# p0-001.net
KiCad netlist of a schematic drawn in EAGLE
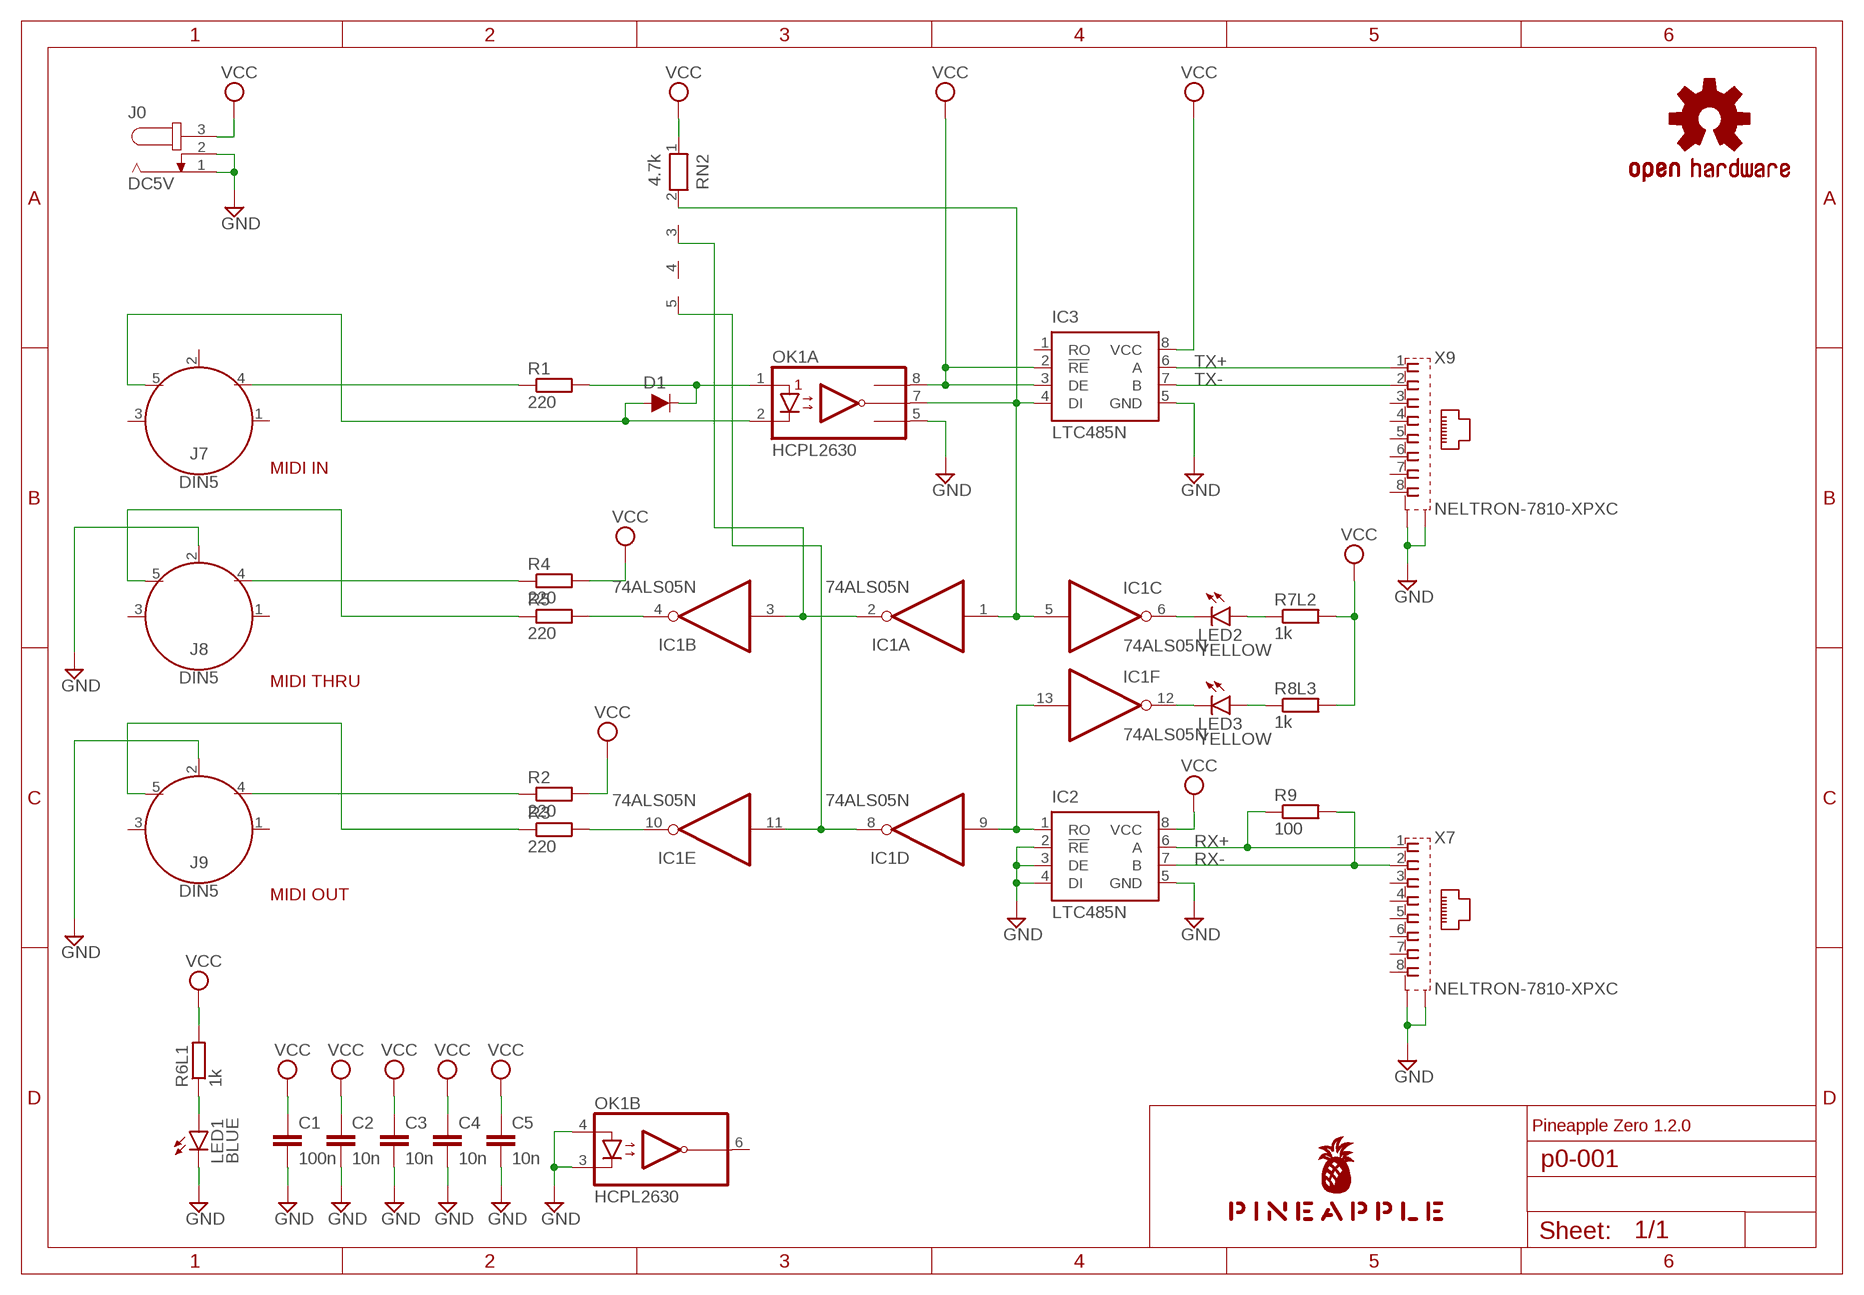
[diagram p0: schematic, sheet 1]

(export (version "E")
  (design (tool "Eeschema 10.0.6"))
  (components
    (comp (ref "C1")
      (value "100n")
      (footprint "eagle-import:C025-024X044")
      (libsource (lib "eagle-import") (part "C-EU025-024X044"))
    )
    (comp (ref "C2")
      (value "10n")
      (footprint "eagle-import:C025-024X044")
      (libsource (lib "eagle-import") (part "C-EU025-024X044"))
    )
    (comp (ref "C3")
      (value "10n")
      (footprint "eagle-import:C025-024X044")
      (libsource (lib "eagle-import") (part "C-EU025-024X044"))
    )
    (comp (ref "C4")
      (value "10n")
      (footprint "eagle-import:C025-024X044")
      (libsource (lib "eagle-import") (part "C-EU025-024X044"))
    )
    (comp (ref "C5")
      (value "10n")
      (footprint "eagle-import:C025-024X044")
      (libsource (lib "eagle-import") (part "C-EU025-024X044"))
    )
    (comp (ref "D1")
      (value "DIODE-1N4148")
      (footprint "eagle-import:DIODE-1N4148")
      (libsource (lib "eagle-import") (part "DIODE-1N4148"))
    )
    (comp (ref "IC1")
      (value "74ALS05N")
      (footprint "eagle-import:DIL14")
      (libsource (lib "eagle-import") (part "7405NALS"))
    )
    (comp (ref "IC2")
      (value "LTC485N")
      (footprint "eagle-import:DIL08")
      (libsource (lib "eagle-import") (part "LTC485N"))
    )
    (comp (ref "IC3")
      (value "LTC485N")
      (footprint "eagle-import:DIL08")
      (libsource (lib "eagle-import") (part "LTC485N"))
    )
    (comp (ref "J0")
      (value "DC5V")
      (footprint "eagle-import:SPC4077")
      (libsource (lib "eagle-import") (part "JACK-PLUG0"))
    )
    (comp (ref "J7")
      (value "DIN5")
      (footprint "eagle-import:DIN5-RA-PTH")
      (libsource (lib "eagle-import") (part "DIN5"))
    )
    (comp (ref "J8")
      (value "DIN5")
      (footprint "eagle-import:DIN5-RA-PTH")
      (libsource (lib "eagle-import") (part "DIN5"))
    )
    (comp (ref "J9")
      (value "DIN5")
      (footprint "eagle-import:DIN5-RA-PTH")
      (libsource (lib "eagle-import") (part "DIN5"))
    )
    (comp (ref "LED1")
      (value "BLUE")
      (footprint "eagle-import:LED3MM")
      (libsource (lib "eagle-import") (part "LED3MM"))
    )
    (comp (ref "LED2")
      (value "YELLOW")
      (footprint "eagle-import:LED3MM")
      (libsource (lib "eagle-import") (part "LED3MM"))
    )
    (comp (ref "LED3")
      (value "YELLOW")
      (footprint "eagle-import:LED3MM")
      (libsource (lib "eagle-import") (part "LED3MM"))
    )
    (comp (ref "LOGO1")
      (value "OSHW-LOGOS-COPPER")
      (footprint "eagle-import:OSHW-LOGO-S_COPPER")
      (libsource (lib "eagle-import") (part "OSHW-LOGOS-COPPER"))
    )
    (comp (ref "OK1")
      (value "HCPL2630")
      (footprint "eagle-import:DIL08")
      (fields (field (name "MF") "AGILENT TECHNOLOGIES") (field (name "MPN") "HCPL-2630-000E"))
      (libsource (lib "eagle-import") (part "HCPL2630"))
    )
    (comp (ref "R1")
      (value "220")
      (footprint "eagle-import:0204_5")
      (libsource (lib "eagle-import") (part "R-EU_0204/5"))
    )
    (comp (ref "R2")
      (value "220")
      (footprint "eagle-import:0204_5")
      (libsource (lib "eagle-import") (part "R-EU_0204/5"))
    )
    (comp (ref "R3")
      (value "220")
      (footprint "eagle-import:0204_5")
      (libsource (lib "eagle-import") (part "R-EU_0204/5"))
    )
    (comp (ref "R4")
      (value "220")
      (footprint "eagle-import:0204_5")
      (libsource (lib "eagle-import") (part "R-EU_0204/5"))
    )
    (comp (ref "R5")
      (value "220")
      (footprint "eagle-import:0204_5")
      (libsource (lib "eagle-import") (part "R-EU_0204/5"))
    )
    (comp (ref "R6L1")
      (value "1k")
      (footprint "eagle-import:0204_5")
      (libsource (lib "eagle-import") (part "R-EU_0204/5"))
    )
    (comp (ref "R7L2")
      (value "1k")
      (footprint "eagle-import:0204_5")
      (libsource (lib "eagle-import") (part "R-EU_0204/5"))
    )
    (comp (ref "R8L3")
      (value "1k")
      (footprint "eagle-import:0204_5")
      (libsource (lib "eagle-import") (part "R-EU_0204/5"))
    )
    (comp (ref "R9")
      (value "100")
      (footprint "eagle-import:0204_5")
      (libsource (lib "eagle-import") (part "R-EU_0204/5"))
    )
    (comp (ref "RN2")
      (value "4.7k")
      (footprint "eagle-import:RN-5")
      (libsource (lib "eagle-import") (part "RN04"))
    )
    (comp (ref "U$1")
      (value "PINEAPPLE450")
      (footprint "eagle-import:PINEAPPLE450")
      (libsource (lib "eagle-import") (part "PINEAPPLE450"))
    )
    (comp (ref "X7")
      (value "NELTRON-7810-XPXC")
      (footprint "eagle-import:NELTRON-7810-XPXC-FOOTPRINT")
      (libsource (lib "eagle-import") (part "NELTRON-7810-XPXC"))
    )
    (comp (ref "X9")
      (value "NELTRON-7810-XPXC")
      (footprint "eagle-import:NELTRON-7810-XPXC-FOOTPRINT")
      (libsource (lib "eagle-import") (part "NELTRON-7810-XPXC"))
    )
  )
  (nets
    (net (code "1") (name "/RX+") (class "Default")
      (node (ref "IC2") (pin "6") (pinfunction "A_6") (pintype "bidirectional"))
      (node (ref "R9") (pin "1") (pinfunction "1_1") (pintype "passive"))
      (node (ref "X7") (pin "1") (pinfunction "1_1") (pintype "passive"))
    )
    (net (code "2") (name "/RX-") (class "Default")
      (node (ref "IC2") (pin "7") (pinfunction "B_7") (pintype "bidirectional"))
      (node (ref "R9") (pin "2") (pinfunction "2_2") (pintype "passive"))
      (node (ref "X7") (pin "2") (pinfunction "2_2") (pintype "passive"))
    )
    (net (code "3") (name "/TX+") (class "Default")
      (node (ref "IC3") (pin "6") (pinfunction "A_6") (pintype "bidirectional"))
      (node (ref "X9") (pin "1") (pinfunction "1_1") (pintype "passive"))
    )
    (net (code "4") (name "/TX-") (class "Default")
      (node (ref "IC3") (pin "7") (pinfunction "B_7") (pintype "bidirectional"))
      (node (ref "X9") (pin "2") (pinfunction "2_2") (pintype "passive"))
    )
    (net (code "5") (name "GND") (class "Default")
      (node (ref "C1") (pin "2") (pinfunction "2_2") (pintype "passive"))
      (node (ref "C2") (pin "2") (pinfunction "2_2") (pintype "passive"))
      (node (ref "C3") (pin "2") (pinfunction "2_2") (pintype "passive"))
      (node (ref "C4") (pin "2") (pinfunction "2_2") (pintype "passive"))
      (node (ref "C5") (pin "2") (pinfunction "2_2") (pintype "passive"))
      (node (ref "IC2") (pin "2") (pinfunction "~{RE}_2") (pintype "input"))
      (node (ref "IC2") (pin "3") (pinfunction "DE_3") (pintype "input"))
      (node (ref "IC2") (pin "4") (pinfunction "DI_4") (pintype "input"))
      (node (ref "IC2") (pin "5") (pinfunction "GND_5") (pintype "input"))
      (node (ref "IC3") (pin "5") (pinfunction "GND_5") (pintype "input"))
      (node (ref "J0") (pin "1") (pinfunction "1_1") (pintype "passive"))
      (node (ref "J0") (pin "2") (pinfunction "2_2") (pintype "passive"))
      (node (ref "J8") (pin "2") (pinfunction "2_2") (pintype "bidirectional"))
      (node (ref "J9") (pin "2") (pinfunction "2_2") (pintype "bidirectional"))
      (node (ref "LED1") (pin "K") (pinfunction "C_K") (pintype "passive"))
      (node (ref "OK1") (pin "3") (pinfunction "C2_3") (pintype "passive"))
      (node (ref "OK1") (pin "4") (pinfunction "A2_4") (pintype "passive"))
      (node (ref "OK1") (pin "5") (pinfunction "GND_5") (pintype "passive"))
      (node (ref "X7") (pin "S1") (pinfunction "S1_S1") (pintype "passive"))
      (node (ref "X7") (pin "S2") (pinfunction "S2_S2") (pintype "passive"))
      (node (ref "X9") (pin "S1") (pinfunction "S1_S1") (pintype "passive"))
      (node (ref "X9") (pin "S2") (pinfunction "S2_S2") (pintype "passive"))
    )
    (net (code "6") (name "Net-(IC1A-I)") (class "Default")
      (node (ref "IC1") (pin "1") (pinfunction "I_1") (pintype "input"))
      (node (ref "IC1") (pin "5") (pinfunction "I_5") (pintype "input"))
      (node (ref "IC3") (pin "4") (pinfunction "DI_4") (pintype "input"))
      (node (ref "OK1") (pin "7") (pinfunction "VO1_7") (pintype "passive"))
      (node (ref "RN2") (pin "2") (pinfunction "2_2") (pintype "passive"))
    )
    (net (code "7") (name "Net-(IC1A-O)") (class "Default")
      (node (ref "IC1") (pin "2") (pinfunction "O_2") (pintype "open_collector"))
      (node (ref "IC1") (pin "3") (pinfunction "I_3") (pintype "input"))
      (node (ref "RN2") (pin "3") (pinfunction "3_3") (pintype "passive"))
    )
    (net (code "8") (name "Net-(IC1B-O)") (class "Default")
      (node (ref "IC1") (pin "4") (pinfunction "O_4") (pintype "open_collector"))
      (node (ref "R5") (pin "2") (pinfunction "2_2") (pintype "passive"))
    )
    (net (code "9") (name "Net-(IC1C-O)") (class "Default")
      (node (ref "IC1") (pin "6") (pinfunction "O_6") (pintype "open_collector"))
      (node (ref "LED2") (pin "K") (pinfunction "C_K") (pintype "passive"))
    )
    (net (code "10") (name "Net-(IC1D-I)") (class "Default")
      (node (ref "IC1") (pin "13") (pinfunction "I_13") (pintype "input"))
      (node (ref "IC1") (pin "9") (pinfunction "I_9") (pintype "input"))
      (node (ref "IC2") (pin "1") (pinfunction "RO_1") (pintype "output"))
    )
    (net (code "11") (name "Net-(IC1D-O)") (class "Default")
      (node (ref "IC1") (pin "11") (pinfunction "I_11") (pintype "input"))
      (node (ref "IC1") (pin "8") (pinfunction "O_8") (pintype "open_collector"))
      (node (ref "RN2") (pin "5") (pinfunction "5_5") (pintype "passive"))
    )
    (net (code "12") (name "Net-(IC1E-O)") (class "Default")
      (node (ref "IC1") (pin "10") (pinfunction "O_10") (pintype "open_collector"))
      (node (ref "R3") (pin "2") (pinfunction "2_2") (pintype "passive"))
    )
    (net (code "13") (name "Net-(IC1F-O)") (class "Default")
      (node (ref "IC1") (pin "12") (pinfunction "O_12") (pintype "open_collector"))
      (node (ref "LED3") (pin "K") (pinfunction "C_K") (pintype "passive"))
    )
    (net (code "14") (name "Net-(J7-Pad4)") (class "Default")
      (node (ref "J7") (pin "4") (pinfunction "4_4") (pintype "bidirectional"))
      (node (ref "R1") (pin "1") (pinfunction "1_1") (pintype "passive"))
    )
    (net (code "15") (name "Net-(J8-Pad4)") (class "Default")
      (node (ref "J8") (pin "4") (pinfunction "4_4") (pintype "bidirectional"))
      (node (ref "R4") (pin "1") (pinfunction "1_1") (pintype "passive"))
    )
    (net (code "16") (name "Net-(J8-Pad5)") (class "Default")
      (node (ref "J8") (pin "5") (pinfunction "5_5") (pintype "bidirectional"))
      (node (ref "R5") (pin "1") (pinfunction "1_1") (pintype "passive"))
    )
    (net (code "17") (name "Net-(J9-Pad4)") (class "Default")
      (node (ref "J9") (pin "4") (pinfunction "4_4") (pintype "bidirectional"))
      (node (ref "R2") (pin "1") (pinfunction "1_1") (pintype "passive"))
    )
    (net (code "18") (name "Net-(J9-Pad5)") (class "Default")
      (node (ref "J9") (pin "5") (pinfunction "5_5") (pintype "bidirectional"))
      (node (ref "R3") (pin "1") (pinfunction "1_1") (pintype "passive"))
    )
    (net (code "19") (name "Net-(LED1-PadA)") (class "Default")
      (node (ref "LED1") (pin "A") (pinfunction "A_A") (pintype "passive"))
      (node (ref "R6L1") (pin "1") (pinfunction "1_1") (pintype "passive"))
    )
    (net (code "20") (name "Net-(LED2-PadA)") (class "Default")
      (node (ref "LED2") (pin "A") (pinfunction "A_A") (pintype "passive"))
      (node (ref "R7L2") (pin "1") (pinfunction "1_1") (pintype "passive"))
    )
    (net (code "21") (name "Net-(LED3-PadA)") (class "Default")
      (node (ref "LED3") (pin "A") (pinfunction "A_A") (pintype "passive"))
      (node (ref "R8L3") (pin "1") (pinfunction "1_1") (pintype "passive"))
    )
    (net (code "22") (name "Net-(OK1A-A1)") (class "Default")
      (node (ref "D1") (pin "C") (pinfunction "C_C") (pintype "passive"))
      (node (ref "OK1") (pin "1") (pinfunction "A1_1") (pintype "passive"))
      (node (ref "R1") (pin "2") (pinfunction "2_2") (pintype "passive"))
    )
    (net (code "23") (name "Net-(OK1A-C1)") (class "Default")
      (node (ref "D1") (pin "A") (pinfunction "A_A") (pintype "passive"))
      (node (ref "J7") (pin "5") (pinfunction "5_5") (pintype "bidirectional"))
      (node (ref "OK1") (pin "2") (pinfunction "C1_2") (pintype "passive"))
    )
    (net (code "24") (name "VCC") (class "Default")
      (node (ref "C1") (pin "1") (pinfunction "1_1") (pintype "passive"))
      (node (ref "C2") (pin "1") (pinfunction "1_1") (pintype "passive"))
      (node (ref "C3") (pin "1") (pinfunction "1_1") (pintype "passive"))
      (node (ref "C4") (pin "1") (pinfunction "1_1") (pintype "passive"))
      (node (ref "C5") (pin "1") (pinfunction "1_1") (pintype "passive"))
      (node (ref "IC2") (pin "8") (pinfunction "VCC_8") (pintype "input"))
      (node (ref "IC3") (pin "2") (pinfunction "~{RE}_2") (pintype "input"))
      (node (ref "IC3") (pin "3") (pinfunction "DE_3") (pintype "input"))
      (node (ref "IC3") (pin "8") (pinfunction "VCC_8") (pintype "input"))
      (node (ref "J0") (pin "3") (pinfunction "3_3") (pintype "passive"))
      (node (ref "OK1") (pin "8") (pinfunction "VCC_8") (pintype "passive"))
      (node (ref "R2") (pin "2") (pinfunction "2_2") (pintype "passive"))
      (node (ref "R4") (pin "2") (pinfunction "2_2") (pintype "passive"))
      (node (ref "R6L1") (pin "2") (pinfunction "2_2") (pintype "passive"))
      (node (ref "R7L2") (pin "2") (pinfunction "2_2") (pintype "passive"))
      (node (ref "R8L3") (pin "2") (pinfunction "2_2") (pintype "passive"))
      (node (ref "RN2") (pin "1") (pinfunction "1_1") (pintype "passive"))
    )
    (net (code "25") (name "unconnected-(IC3-RO-Pad1)") (class "Default")
      (node (ref "IC3") (pin "1") (pinfunction "RO_1") (pintype "output"))
    )
    (net (code "26") (name "unconnected-(J7-Pad1)") (class "Default")
      (node (ref "J7") (pin "1") (pinfunction "1_1") (pintype "bidirectional"))
    )
    (net (code "27") (name "unconnected-(J7-Pad2)") (class "Default")
      (node (ref "J7") (pin "2") (pinfunction "2_2") (pintype "bidirectional"))
    )
    (net (code "28") (name "unconnected-(J7-Pad3)") (class "Default")
      (node (ref "J7") (pin "3") (pinfunction "3_3") (pintype "bidirectional"))
    )
    (net (code "29") (name "unconnected-(J8-Pad1)") (class "Default")
      (node (ref "J8") (pin "1") (pinfunction "1_1") (pintype "bidirectional"))
    )
    (net (code "30") (name "unconnected-(J8-Pad3)") (class "Default")
      (node (ref "J8") (pin "3") (pinfunction "3_3") (pintype "bidirectional"))
    )
    (net (code "31") (name "unconnected-(J9-Pad1)") (class "Default")
      (node (ref "J9") (pin "1") (pinfunction "1_1") (pintype "bidirectional"))
    )
    (net (code "32") (name "unconnected-(J9-Pad3)") (class "Default")
      (node (ref "J9") (pin "3") (pinfunction "3_3") (pintype "bidirectional"))
    )
    (net (code "33") (name "unconnected-(OK1B-VO2-Pad6)") (class "Default")
      (node (ref "OK1") (pin "6") (pinfunction "VO2_6") (pintype "passive"))
    )
    (net (code "34") (name "unconnected-(RN2-Pad4)") (class "Default")
      (node (ref "RN2") (pin "4") (pinfunction "4_4") (pintype "passive"))
    )
    (net (code "35") (name "unconnected-(X7-Pad3)") (class "Default")
      (node (ref "X7") (pin "3") (pinfunction "3_3") (pintype "passive"))
    )
    (net (code "36") (name "unconnected-(X7-Pad4)") (class "Default")
      (node (ref "X7") (pin "4") (pinfunction "4_4") (pintype "passive"))
    )
    (net (code "37") (name "unconnected-(X7-Pad5)") (class "Default")
      (node (ref "X7") (pin "5") (pinfunction "5_5") (pintype "passive"))
    )
    (net (code "38") (name "unconnected-(X7-Pad6)") (class "Default")
      (node (ref "X7") (pin "6") (pinfunction "6_6") (pintype "passive"))
    )
    (net (code "39") (name "unconnected-(X7-Pad7)") (class "Default")
      (node (ref "X7") (pin "7") (pinfunction "7_7") (pintype "passive"))
    )
    (net (code "40") (name "unconnected-(X7-Pad8)") (class "Default")
      (node (ref "X7") (pin "8") (pinfunction "8_8") (pintype "passive"))
    )
    (net (code "41") (name "unconnected-(X9-Pad3)") (class "Default")
      (node (ref "X9") (pin "3") (pinfunction "3_3") (pintype "passive"))
    )
    (net (code "42") (name "unconnected-(X9-Pad4)") (class "Default")
      (node (ref "X9") (pin "4") (pinfunction "4_4") (pintype "passive"))
    )
    (net (code "43") (name "unconnected-(X9-Pad5)") (class "Default")
      (node (ref "X9") (pin "5") (pinfunction "5_5") (pintype "passive"))
    )
    (net (code "44") (name "unconnected-(X9-Pad6)") (class "Default")
      (node (ref "X9") (pin "6") (pinfunction "6_6") (pintype "passive"))
    )
    (net (code "45") (name "unconnected-(X9-Pad7)") (class "Default")
      (node (ref "X9") (pin "7") (pinfunction "7_7") (pintype "passive"))
    )
    (net (code "46") (name "unconnected-(X9-Pad8)") (class "Default")
      (node (ref "X9") (pin "8") (pinfunction "8_8") (pintype "passive"))
    )
  )
)
